# ProProject_flex_ir_golf_2024-07-23.net
KiCad netlist of a schematic drawn in EasyEDA Pro
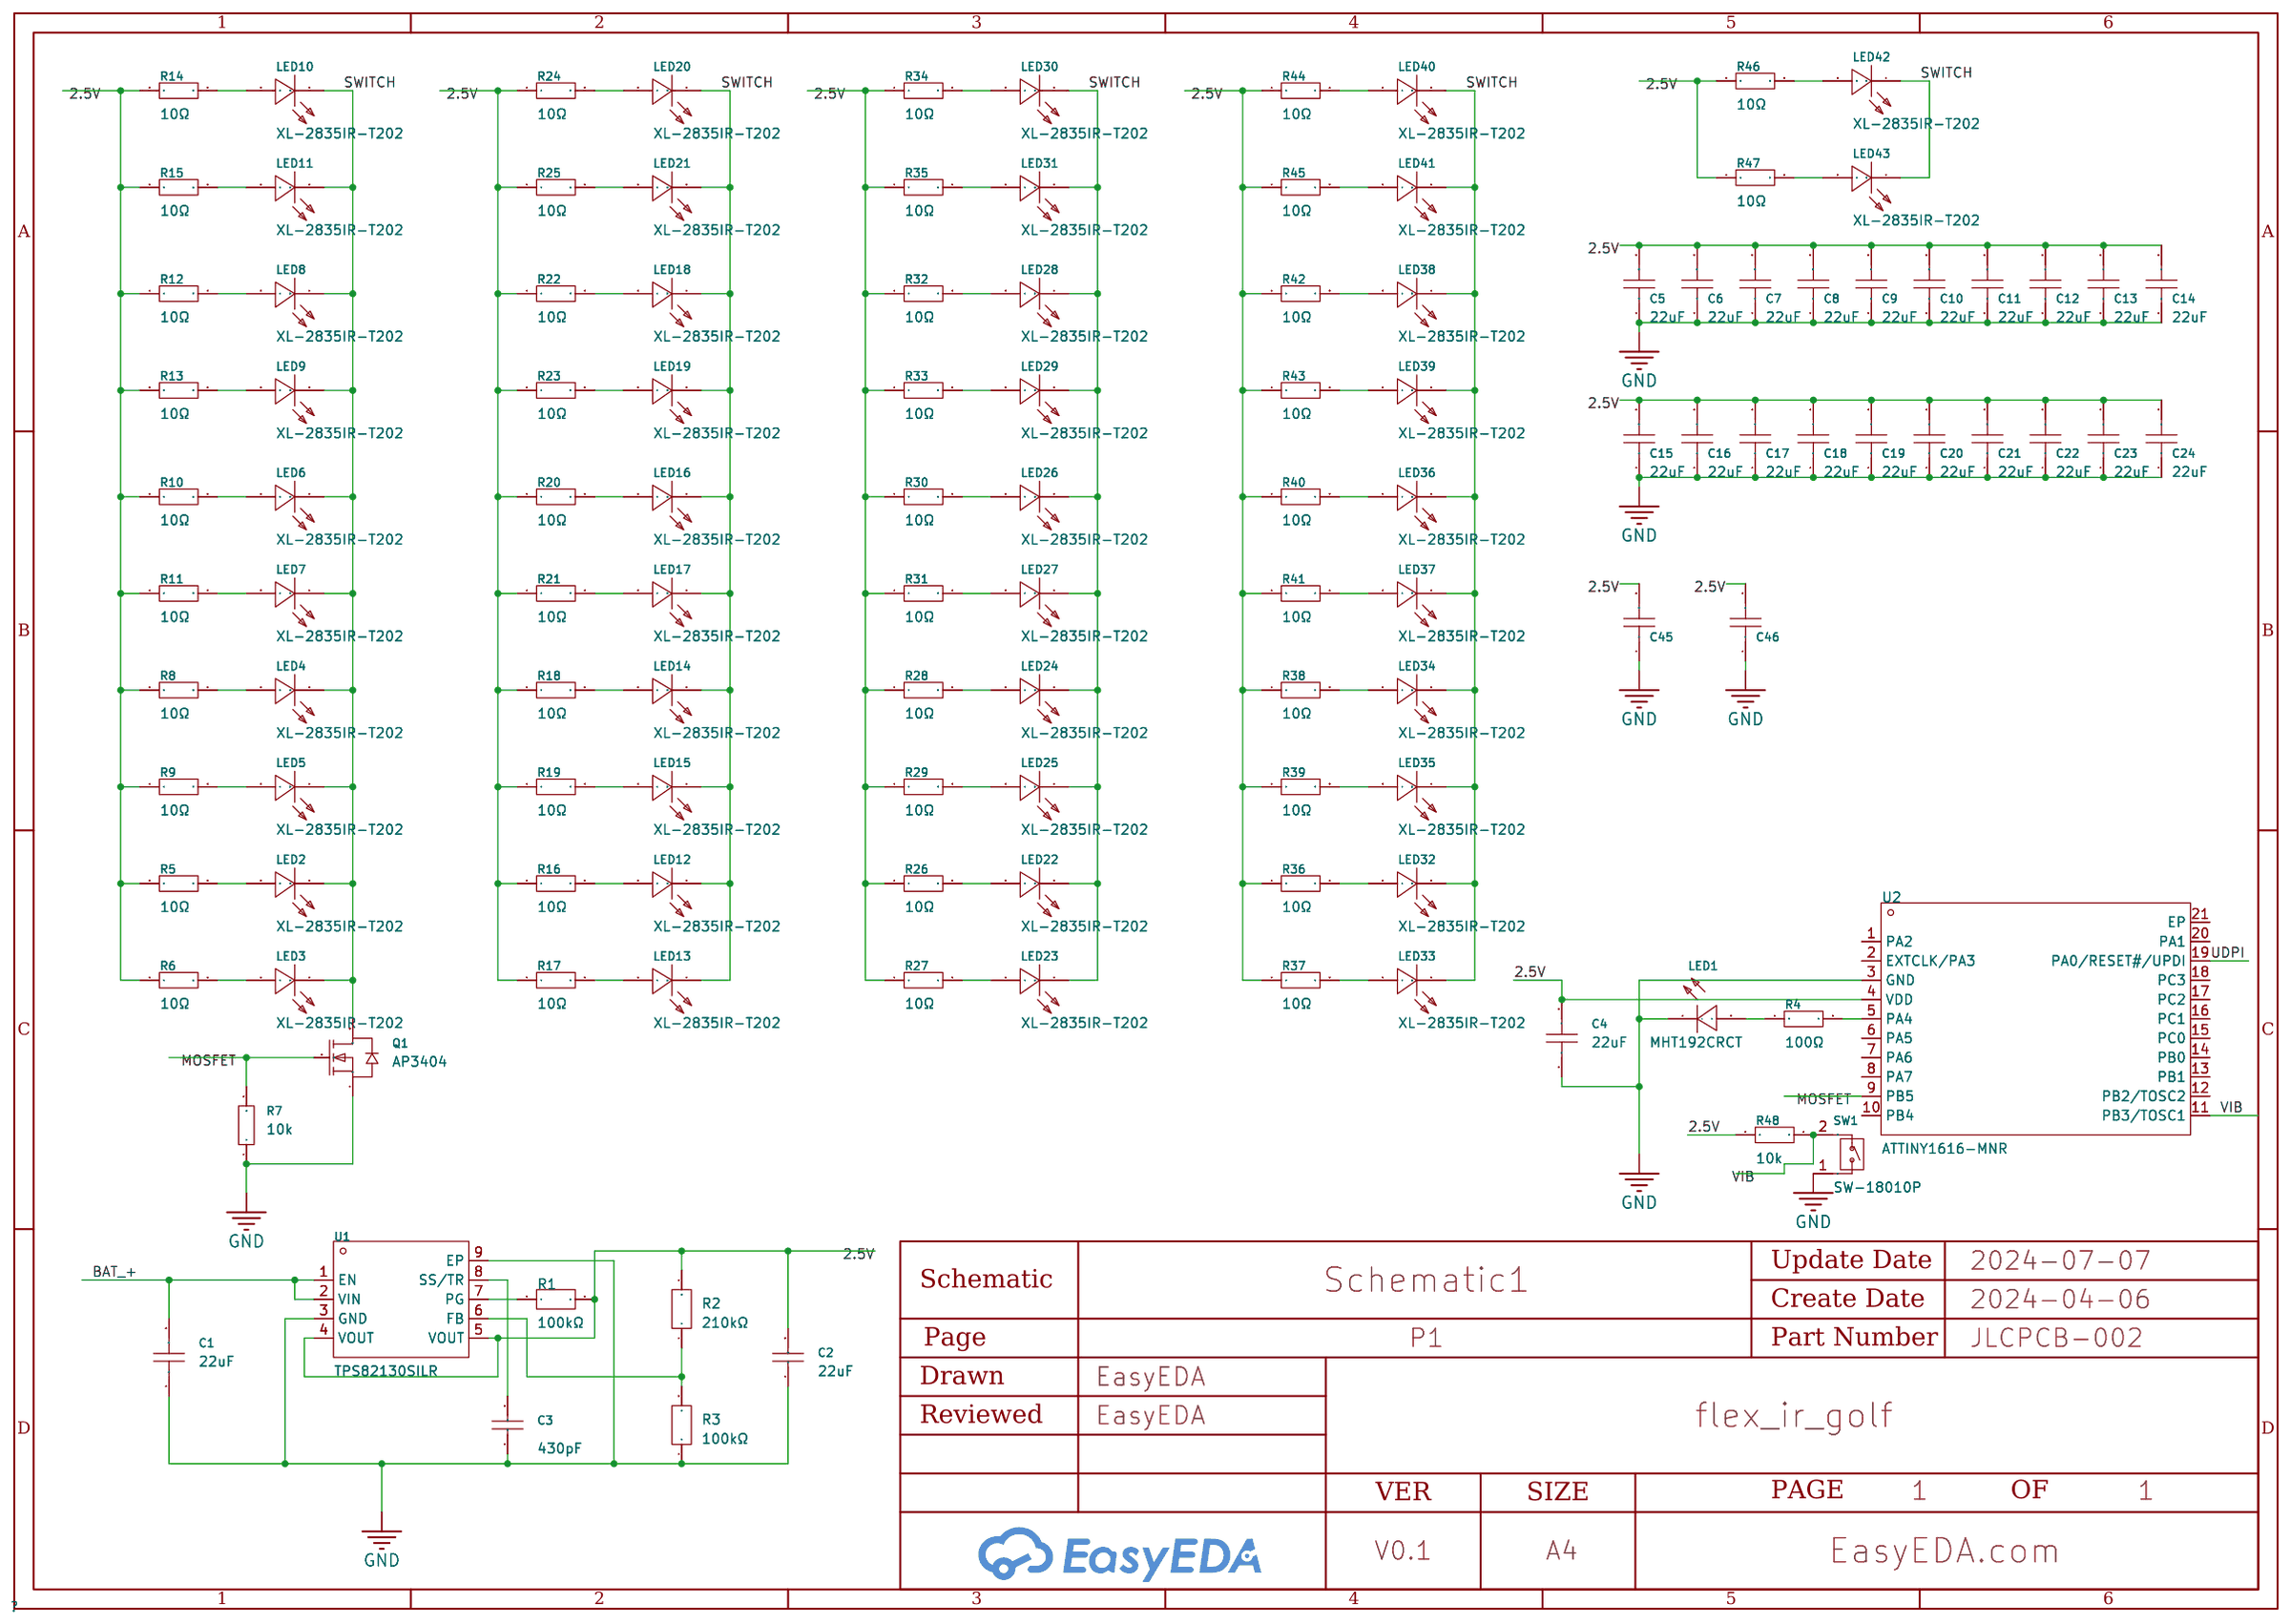
[diagram p0: schematic sheet]

(export (version "E")
  (design (tool "Eeschema 10.0.6"))
  (components
    (comp (ref "C1")
      (value "22uF")
      (footprint "easyedapro:C0603")
      (fields
        (field (name "Manufacturer Part") "GRM188R60J226MEA0D")
        (field (name "Manufacturer") "muRata(村田)")
      )
      (libsource (lib "easyedapro") (part "GRM188R60J226MEA0D"))
    )
    (comp (ref "C2")
      (value "22uF")
      (footprint "easyedapro:C0805")
      (fields
        (field (name "Manufacturer Part") "GRM21BR60J226ME39L")
        (field (name "Manufacturer") "muRata(村田)")
      )
      (libsource (lib "easyedapro") (part "GRM21BR60J226ME39L"))
    )
    (comp (ref "C3")
      (value "1uF")
      (footprint "easyedapro:C0402")
      (fields (field (name "Manufacturer Part") "GRM1555C1H431GA01D"))
      (libsource (lib "easyedapro") (part "CL05A105KP5NNNC"))
    )
    (comp (ref "C4")
      (value "22uF")
      (footprint "easyedapro:C0603")
      (fields
        (field (name "Manufacturer Part") "GRM188R60J226MEA0D")
        (field (name "Manufacturer") "muRata(村田)")
      )
      (libsource (lib "easyedapro") (part "GRM188R60J226MEA0D"))
    )
    (comp (ref "C5")
      (value "22uF")
      (footprint "easyedapro:C0603")
      (fields
        (field (name "Manufacturer Part") "GRM188R60J226MEA0D")
        (field (name "Manufacturer") "muRata(村田)")
      )
      (libsource (lib "easyedapro") (part "GRM188R60J226MEA0D"))
    )
    (comp (ref "C6")
      (value "22uF")
      (footprint "easyedapro:C0603")
      (fields
        (field (name "Manufacturer Part") "GRM188R60J226MEA0D")
        (field (name "Manufacturer") "muRata(村田)")
      )
      (libsource (lib "easyedapro") (part "GRM188R60J226MEA0D"))
    )
    (comp (ref "C7")
      (value "22uF")
      (footprint "easyedapro:C0603")
      (fields
        (field (name "Manufacturer Part") "GRM188R60J226MEA0D")
        (field (name "Manufacturer") "muRata(村田)")
      )
      (libsource (lib "easyedapro") (part "GRM188R60J226MEA0D"))
    )
    (comp (ref "C8")
      (value "22uF")
      (footprint "easyedapro:C0603")
      (fields
        (field (name "Manufacturer Part") "GRM188R60J226MEA0D")
        (field (name "Manufacturer") "muRata(村田)")
      )
      (libsource (lib "easyedapro") (part "GRM188R60J226MEA0D"))
    )
    (comp (ref "C9")
      (value "22uF")
      (footprint "easyedapro:C0603")
      (fields
        (field (name "Manufacturer Part") "GRM188R60J226MEA0D")
        (field (name "Manufacturer") "muRata(村田)")
      )
      (libsource (lib "easyedapro") (part "GRM188R60J226MEA0D"))
    )
    (comp (ref "C10")
      (value "22uF")
      (footprint "easyedapro:C0603")
      (fields
        (field (name "Manufacturer Part") "GRM188R60J226MEA0D")
        (field (name "Manufacturer") "muRata(村田)")
      )
      (libsource (lib "easyedapro") (part "GRM188R60J226MEA0D"))
    )
    (comp (ref "C11")
      (value "22uF")
      (footprint "easyedapro:C0603")
      (fields
        (field (name "Manufacturer Part") "GRM188R60J226MEA0D")
        (field (name "Manufacturer") "muRata(村田)")
      )
      (libsource (lib "easyedapro") (part "GRM188R60J226MEA0D"))
    )
    (comp (ref "C12")
      (value "22uF")
      (footprint "easyedapro:C0603")
      (fields
        (field (name "Manufacturer Part") "GRM188R60J226MEA0D")
        (field (name "Manufacturer") "muRata(村田)")
      )
      (libsource (lib "easyedapro") (part "GRM188R60J226MEA0D"))
    )
    (comp (ref "C13")
      (value "22uF")
      (footprint "easyedapro:C0603")
      (fields
        (field (name "Manufacturer Part") "GRM188R60J226MEA0D")
        (field (name "Manufacturer") "muRata(村田)")
      )
      (libsource (lib "easyedapro") (part "GRM188R60J226MEA0D"))
    )
    (comp (ref "C14")
      (value "22uF")
      (footprint "easyedapro:C0603")
      (fields
        (field (name "Manufacturer Part") "GRM188R60J226MEA0D")
        (field (name "Manufacturer") "muRata(村田)")
      )
      (libsource (lib "easyedapro") (part "GRM188R60J226MEA0D"))
    )
    (comp (ref "C15")
      (value "22uF")
      (footprint "easyedapro:C0603")
      (fields
        (field (name "Manufacturer Part") "GRM188R60J226MEA0D")
        (field (name "Manufacturer") "muRata(村田)")
      )
      (libsource (lib "easyedapro") (part "GRM188R60J226MEA0D"))
    )
    (comp (ref "C16")
      (value "22uF")
      (footprint "easyedapro:C0603")
      (fields
        (field (name "Manufacturer Part") "GRM188R60J226MEA0D")
        (field (name "Manufacturer") "muRata(村田)")
      )
      (libsource (lib "easyedapro") (part "GRM188R60J226MEA0D"))
    )
    (comp (ref "C17")
      (value "22uF")
      (footprint "easyedapro:C0603")
      (fields
        (field (name "Manufacturer Part") "GRM188R60J226MEA0D")
        (field (name "Manufacturer") "muRata(村田)")
      )
      (libsource (lib "easyedapro") (part "GRM188R60J226MEA0D"))
    )
    (comp (ref "C18")
      (value "22uF")
      (footprint "easyedapro:C0603")
      (fields
        (field (name "Manufacturer Part") "GRM188R60J226MEA0D")
        (field (name "Manufacturer") "muRata(村田)")
      )
      (libsource (lib "easyedapro") (part "GRM188R60J226MEA0D"))
    )
    (comp (ref "C19")
      (value "22uF")
      (footprint "easyedapro:C0603")
      (fields
        (field (name "Manufacturer Part") "GRM188R60J226MEA0D")
        (field (name "Manufacturer") "muRata(村田)")
      )
      (libsource (lib "easyedapro") (part "GRM188R60J226MEA0D"))
    )
    (comp (ref "C20")
      (value "22uF")
      (footprint "easyedapro:C0603")
      (fields
        (field (name "Manufacturer Part") "GRM188R60J226MEA0D")
        (field (name "Manufacturer") "muRata(村田)")
      )
      (libsource (lib "easyedapro") (part "GRM188R60J226MEA0D"))
    )
    (comp (ref "C21")
      (value "22uF")
      (footprint "easyedapro:C0603")
      (fields
        (field (name "Manufacturer Part") "GRM188R60J226MEA0D")
        (field (name "Manufacturer") "muRata(村田)")
      )
      (libsource (lib "easyedapro") (part "GRM188R60J226MEA0D"))
    )
    (comp (ref "C22")
      (value "22uF")
      (footprint "easyedapro:C0603")
      (fields
        (field (name "Manufacturer Part") "GRM188R60J226MEA0D")
        (field (name "Manufacturer") "muRata(村田)")
      )
      (libsource (lib "easyedapro") (part "GRM188R60J226MEA0D"))
    )
    (comp (ref "C23")
      (value "22uF")
      (footprint "easyedapro:C0603")
      (fields
        (field (name "Manufacturer Part") "GRM188R60J226MEA0D")
        (field (name "Manufacturer") "muRata(村田)")
      )
      (libsource (lib "easyedapro") (part "GRM188R60J226MEA0D"))
    )
    (comp (ref "C24")
      (value "22uF")
      (footprint "easyedapro:C0603")
      (fields
        (field (name "Manufacturer Part") "GRM188R60J226MEA0D")
        (field (name "Manufacturer") "muRata(村田)")
      )
      (libsource (lib "easyedapro") (part "GRM188R60J226MEA0D"))
    )
    (comp (ref "C45")
      (value "22uF")
      (footprint "easyedapro:C0603")
      (fields
        (field (name "Manufacturer Part") "GRM188R60J226MEA0D")
        (field (name "Manufacturer") "muRata(村田)")
      )
      (libsource (lib "easyedapro") (part "GRM188R60J226MEA0D"))
    )
    (comp (ref "C46")
      (value "22uF")
      (footprint "easyedapro:C0603")
      (fields
        (field (name "Manufacturer Part") "GRM188R60J226MEA0D")
        (field (name "Manufacturer") "muRata(村田)")
      )
      (libsource (lib "easyedapro") (part "GRM188R60J226MEA0D"))
    )
    (comp (ref "LED1")
      (value "MHT192CRCT")
      (footprint "easyedapro:LED0603-RD")
      (fields (field (name "Manufacturer") "MEIHUA(美华)"))
      (libsource (lib "easyedapro") (part "MHT192CRCT"))
    )
    (comp (ref "LED2")
      (value "XL-2835IR-T202")
      (footprint "easyedapro:LED-SMD_L128-XX80CB3500001")
      (description "Emitted Color:White")
      (fields (field (name "Manufacturer") "Lumileds(亮锐)"))
      (libsource (lib "easyedapro") (part "L128-4080CB3500001"))
    )
    (comp (ref "LED3")
      (value "XL-2835IR-T202")
      (footprint "easyedapro:LED-SMD_L128-XX80CB3500001")
      (description "Emitted Color:White")
      (fields (field (name "Manufacturer") "Lumileds(亮锐)"))
      (libsource (lib "easyedapro") (part "L128-4080CB3500001"))
    )
    (comp (ref "LED4")
      (value "XL-2835IR-T202")
      (footprint "easyedapro:LED-SMD_L128-XX80CB3500001")
      (description "Emitted Color:White")
      (fields (field (name "Manufacturer") "Lumileds(亮锐)"))
      (libsource (lib "easyedapro") (part "L128-4080CB3500001"))
    )
    (comp (ref "LED5")
      (value "XL-2835IR-T202")
      (footprint "easyedapro:LED-SMD_L128-XX80CB3500001")
      (description "Emitted Color:White")
      (fields (field (name "Manufacturer") "Lumileds(亮锐)"))
      (libsource (lib "easyedapro") (part "L128-4080CB3500001"))
    )
    (comp (ref "LED6")
      (value "XL-2835IR-T202")
      (footprint "easyedapro:LED-SMD_L128-XX80CB3500001")
      (description "Emitted Color:White")
      (fields (field (name "Manufacturer") "Lumileds(亮锐)"))
      (libsource (lib "easyedapro") (part "L128-4080CB3500001"))
    )
    (comp (ref "LED7")
      (value "XL-2835IR-T202")
      (footprint "easyedapro:LED-SMD_L128-XX80CB3500001")
      (description "Emitted Color:White")
      (fields (field (name "Manufacturer") "Lumileds(亮锐)"))
      (libsource (lib "easyedapro") (part "L128-4080CB3500001"))
    )
    (comp (ref "LED8")
      (value "XL-2835IR-T202")
      (footprint "easyedapro:LED-SMD_L128-XX80CB3500001")
      (description "Emitted Color:White")
      (fields (field (name "Manufacturer") "Lumileds(亮锐)"))
      (libsource (lib "easyedapro") (part "L128-4080CB3500001"))
    )
    (comp (ref "LED9")
      (value "XL-2835IR-T202")
      (footprint "easyedapro:LED-SMD_L128-XX80CB3500001")
      (description "Emitted Color:White")
      (fields (field (name "Manufacturer") "Lumileds(亮锐)"))
      (libsource (lib "easyedapro") (part "L128-4080CB3500001"))
    )
    (comp (ref "LED10")
      (value "XL-2835IR-T202")
      (footprint "easyedapro:LED-SMD_L128-XX80CB3500001")
      (description "Emitted Color:White")
      (fields (field (name "Manufacturer") "Lumileds(亮锐)"))
      (libsource (lib "easyedapro") (part "L128-4080CB3500001"))
    )
    (comp (ref "LED11")
      (value "XL-2835IR-T202")
      (footprint "easyedapro:LED-SMD_L128-XX80CB3500001")
      (description "Emitted Color:White")
      (fields (field (name "Manufacturer") "Lumileds(亮锐)"))
      (libsource (lib "easyedapro") (part "L128-4080CB3500001"))
    )
    (comp (ref "LED12")
      (value "XL-2835IR-T202")
      (footprint "easyedapro:LED-SMD_L128-XX80CB3500001")
      (description "Emitted Color:White")
      (fields (field (name "Manufacturer") "Lumileds(亮锐)"))
      (libsource (lib "easyedapro") (part "L128-4080CB3500001"))
    )
    (comp (ref "LED13")
      (value "XL-2835IR-T202")
      (footprint "easyedapro:LED-SMD_L128-XX80CB3500001")
      (description "Emitted Color:White")
      (fields (field (name "Manufacturer") "Lumileds(亮锐)"))
      (libsource (lib "easyedapro") (part "L128-4080CB3500001"))
    )
    (comp (ref "LED14")
      (value "XL-2835IR-T202")
      (footprint "easyedapro:LED-SMD_L128-XX80CB3500001")
      (description "Emitted Color:White")
      (fields (field (name "Manufacturer") "Lumileds(亮锐)"))
      (libsource (lib "easyedapro") (part "L128-4080CB3500001"))
    )
    (comp (ref "LED15")
      (value "XL-2835IR-T202")
      (footprint "easyedapro:LED-SMD_L128-XX80CB3500001")
      (description "Emitted Color:White")
      (fields (field (name "Manufacturer") "Lumileds(亮锐)"))
      (libsource (lib "easyedapro") (part "L128-4080CB3500001"))
    )
    (comp (ref "LED16")
      (value "XL-2835IR-T202")
      (footprint "easyedapro:LED-SMD_L128-XX80CB3500001")
      (description "Emitted Color:White")
      (fields (field (name "Manufacturer") "Lumileds(亮锐)"))
      (libsource (lib "easyedapro") (part "L128-4080CB3500001"))
    )
    (comp (ref "LED17")
      (value "XL-2835IR-T202")
      (footprint "easyedapro:LED-SMD_L128-XX80CB3500001")
      (description "Emitted Color:White")
      (fields (field (name "Manufacturer") "Lumileds(亮锐)"))
      (libsource (lib "easyedapro") (part "L128-4080CB3500001"))
    )
    (comp (ref "LED18")
      (value "XL-2835IR-T202")
      (footprint "easyedapro:LED-SMD_L128-XX80CB3500001")
      (description "Emitted Color:White")
      (fields (field (name "Manufacturer") "Lumileds(亮锐)"))
      (libsource (lib "easyedapro") (part "L128-4080CB3500001"))
    )
    (comp (ref "LED19")
      (value "XL-2835IR-T202")
      (footprint "easyedapro:LED-SMD_L128-XX80CB3500001")
      (description "Emitted Color:White")
      (fields (field (name "Manufacturer") "Lumileds(亮锐)"))
      (libsource (lib "easyedapro") (part "L128-4080CB3500001"))
    )
    (comp (ref "LED20")
      (value "XL-2835IR-T202")
      (footprint "easyedapro:LED-SMD_L128-XX80CB3500001")
      (description "Emitted Color:White")
      (fields (field (name "Manufacturer") "Lumileds(亮锐)"))
      (libsource (lib "easyedapro") (part "L128-4080CB3500001"))
    )
    (comp (ref "LED21")
      (value "XL-2835IR-T202")
      (footprint "easyedapro:LED-SMD_L128-XX80CB3500001")
      (description "Emitted Color:White")
      (fields (field (name "Manufacturer") "Lumileds(亮锐)"))
      (libsource (lib "easyedapro") (part "L128-4080CB3500001"))
    )
    (comp (ref "LED22")
      (value "XL-2835IR-T202")
      (footprint "easyedapro:LED-SMD_L128-XX80CB3500001")
      (description "Emitted Color:White")
      (fields (field (name "Manufacturer") "Lumileds(亮锐)"))
      (libsource (lib "easyedapro") (part "L128-4080CB3500001"))
    )
    (comp (ref "LED23")
      (value "XL-2835IR-T202")
      (footprint "easyedapro:LED-SMD_L128-XX80CB3500001")
      (description "Emitted Color:White")
      (fields (field (name "Manufacturer") "Lumileds(亮锐)"))
      (libsource (lib "easyedapro") (part "L128-4080CB3500001"))
    )
    (comp (ref "LED24")
      (value "XL-2835IR-T202")
      (footprint "easyedapro:LED-SMD_L128-XX80CB3500001")
      (description "Emitted Color:White")
      (fields (field (name "Manufacturer") "Lumileds(亮锐)"))
      (libsource (lib "easyedapro") (part "L128-4080CB3500001"))
    )
    (comp (ref "LED25")
      (value "XL-2835IR-T202")
      (footprint "easyedapro:LED-SMD_L128-XX80CB3500001")
      (description "Emitted Color:White")
      (fields (field (name "Manufacturer") "Lumileds(亮锐)"))
      (libsource (lib "easyedapro") (part "L128-4080CB3500001"))
    )
    (comp (ref "LED26")
      (value "XL-2835IR-T202")
      (footprint "easyedapro:LED-SMD_L128-XX80CB3500001")
      (description "Emitted Color:White")
      (fields (field (name "Manufacturer") "Lumileds(亮锐)"))
      (libsource (lib "easyedapro") (part "L128-4080CB3500001"))
    )
    (comp (ref "LED27")
      (value "XL-2835IR-T202")
      (footprint "easyedapro:LED-SMD_L128-XX80CB3500001")
      (description "Emitted Color:White")
      (fields (field (name "Manufacturer") "Lumileds(亮锐)"))
      (libsource (lib "easyedapro") (part "L128-4080CB3500001"))
    )
    (comp (ref "LED28")
      (value "XL-2835IR-T202")
      (footprint "easyedapro:LED-SMD_L128-XX80CB3500001")
      (description "Emitted Color:White")
      (fields (field (name "Manufacturer") "Lumileds(亮锐)"))
      (libsource (lib "easyedapro") (part "L128-4080CB3500001"))
    )
    (comp (ref "LED29")
      (value "XL-2835IR-T202")
      (footprint "easyedapro:LED-SMD_L128-XX80CB3500001")
      (description "Emitted Color:White")
      (fields (field (name "Manufacturer") "Lumileds(亮锐)"))
      (libsource (lib "easyedapro") (part "L128-4080CB3500001"))
    )
    (comp (ref "LED30")
      (value "XL-2835IR-T202")
      (footprint "easyedapro:LED-SMD_L128-XX80CB3500001")
      (description "Emitted Color:White")
      (fields (field (name "Manufacturer") "Lumileds(亮锐)"))
      (libsource (lib "easyedapro") (part "L128-4080CB3500001"))
    )
    (comp (ref "LED31")
      (value "XL-2835IR-T202")
      (footprint "easyedapro:LED-SMD_L128-XX80CB3500001")
      (description "Emitted Color:White")
      (fields (field (name "Manufacturer") "Lumileds(亮锐)"))
      (libsource (lib "easyedapro") (part "L128-4080CB3500001"))
    )
    (comp (ref "LED32")
      (value "XL-2835IR-T202")
      (footprint "easyedapro:LED-SMD_L128-XX80CB3500001")
      (description "Emitted Color:White")
      (fields (field (name "Manufacturer") "Lumileds(亮锐)"))
      (libsource (lib "easyedapro") (part "L128-4080CB3500001"))
    )
    (comp (ref "LED33")
      (value "XL-2835IR-T202")
      (footprint "easyedapro:LED-SMD_L128-XX80CB3500001")
      (description "Emitted Color:White")
      (fields (field (name "Manufacturer") "Lumileds(亮锐)"))
      (libsource (lib "easyedapro") (part "L128-4080CB3500001"))
    )
    (comp (ref "LED34")
      (value "XL-2835IR-T202")
      (footprint "easyedapro:LED-SMD_L128-XX80CB3500001")
      (description "Emitted Color:White")
      (fields (field (name "Manufacturer") "Lumileds(亮锐)"))
      (libsource (lib "easyedapro") (part "L128-4080CB3500001"))
    )
    (comp (ref "LED35")
      (value "XL-2835IR-T202")
      (footprint "easyedapro:LED-SMD_L128-XX80CB3500001")
      (description "Emitted Color:White")
      (fields (field (name "Manufacturer") "Lumileds(亮锐)"))
      (libsource (lib "easyedapro") (part "L128-4080CB3500001"))
    )
    (comp (ref "LED36")
      (value "XL-2835IR-T202")
      (footprint "easyedapro:LED-SMD_L128-XX80CB3500001")
      (description "Emitted Color:White")
      (fields (field (name "Manufacturer") "Lumileds(亮锐)"))
      (libsource (lib "easyedapro") (part "L128-4080CB3500001"))
    )
    (comp (ref "LED37")
      (value "XL-2835IR-T202")
      (footprint "easyedapro:LED-SMD_L128-XX80CB3500001")
      (description "Emitted Color:White")
      (fields (field (name "Manufacturer") "Lumileds(亮锐)"))
      (libsource (lib "easyedapro") (part "L128-4080CB3500001"))
    )
    (comp (ref "LED38")
      (value "XL-2835IR-T202")
      (footprint "easyedapro:LED-SMD_L128-XX80CB3500001")
      (description "Emitted Color:White")
      (fields (field (name "Manufacturer") "Lumileds(亮锐)"))
      (libsource (lib "easyedapro") (part "L128-4080CB3500001"))
    )
    (comp (ref "LED39")
      (value "XL-2835IR-T202")
      (footprint "easyedapro:LED-SMD_L128-XX80CB3500001")
      (description "Emitted Color:White")
      (fields (field (name "Manufacturer") "Lumileds(亮锐)"))
      (libsource (lib "easyedapro") (part "L128-4080CB3500001"))
    )
    (comp (ref "LED40")
      (value "XL-2835IR-T202")
      (footprint "easyedapro:LED-SMD_L128-XX80CB3500001")
      (description "Emitted Color:White")
      (fields (field (name "Manufacturer") "Lumileds(亮锐)"))
      (libsource (lib "easyedapro") (part "L128-4080CB3500001"))
    )
    (comp (ref "LED41")
      (value "XL-2835IR-T202")
      (footprint "easyedapro:LED-SMD_L128-XX80CB3500001")
      (description "Emitted Color:White")
      (fields (field (name "Manufacturer") "Lumileds(亮锐)"))
      (libsource (lib "easyedapro") (part "L128-4080CB3500001"))
    )
    (comp (ref "LED42")
      (value "XL-2835IR-T202")
      (footprint "easyedapro:LED-SMD_L128-XX80CB3500001")
      (description "Emitted Color:White")
      (fields (field (name "Manufacturer") "Lumileds(亮锐)"))
      (libsource (lib "easyedapro") (part "L128-4080CB3500001"))
    )
    (comp (ref "LED43")
      (value "XL-2835IR-T202")
      (footprint "easyedapro:LED-SMD_L128-XX80CB3500001")
      (description "Emitted Color:White")
      (fields (field (name "Manufacturer") "Lumileds(亮锐)"))
      (libsource (lib "easyedapro") (part "L128-4080CB3500001"))
    )
    (comp (ref "Q1")
      (value "AP3404")
      (footprint "easyedapro:SOT-23-3_L2.9-W1.3-P1.90-LS2.4-BR-2")
      (fields (field (name "Manufacturer") "ALLPOWER(铨力)"))
      (libsource (lib "easyedapro") (part "AP3404"))
    )
    (comp (ref "R1")
      (value "100kΩ")
      (footprint "easyedapro:R0402")
      (fields
        (field (name "Manufacturer Part") "CRCW0402100KFKED")
        (field (name "Manufacturer") "VISHAY(威世)")
      )
      (libsource (lib "easyedapro") (part "CRCW0402100KFKED"))
    )
    (comp (ref "R2")
      (value "210kΩ")
      (footprint "easyedapro:R0402")
      (fields
        (field (name "Manufacturer Part") "CRCW0402210KFKED")
        (field (name "Manufacturer") "VISHAY(威世)")
      )
      (libsource (lib "easyedapro") (part "CRCW0402210KFKED"))
    )
    (comp (ref "R3")
      (value "100kΩ")
      (footprint "easyedapro:R0402")
      (fields
        (field (name "Manufacturer Part") "CRCW0402100KFKED")
        (field (name "Manufacturer") "VISHAY(威世)")
      )
      (libsource (lib "easyedapro") (part "CRCW0402100KFKED"))
    )
    (comp (ref "R4")
      (value "100Ω")
      (footprint "easyedapro:R0402")
      (fields
        (field (name "Manufacturer Part") "0402WGF1000TCE")
        (field (name "Manufacturer") "UNI-ROYAL(厚声)")
      )
      (libsource (lib "easyedapro") (part "0402WGF1000TCE"))
    )
    (comp (ref "R5")
      (value "10Ω")
      (footprint "easyedapro:R0603")
      (fields
        (field (name "Manufacturer Part") "0603WAF100JT5E")
        (field (name "Manufacturer") "UNI-ROYAL(厚声)")
      )
      (libsource (lib "easyedapro") (part "0603WAF100JT5E"))
    )
    (comp (ref "R6")
      (value "10Ω")
      (footprint "easyedapro:R0603")
      (fields
        (field (name "Manufacturer Part") "0603WAF100JT5E")
        (field (name "Manufacturer") "UNI-ROYAL(厚声)")
      )
      (libsource (lib "easyedapro") (part "0603WAF100JT5E"))
    )
    (comp (ref "R7")
      (value "10k")
      (footprint "easyedapro:R0603")
      (fields
        (field (name "Manufacturer Part") "0603WAF100JT5E")
        (field (name "Manufacturer") "UNI-ROYAL(厚声)")
      )
      (libsource (lib "easyedapro") (part "0603WAF100JT5E"))
    )
    (comp (ref "R8")
      (value "10Ω")
      (footprint "easyedapro:R0603")
      (fields
        (field (name "Manufacturer Part") "0603WAF100JT5E")
        (field (name "Manufacturer") "UNI-ROYAL(厚声)")
      )
      (libsource (lib "easyedapro") (part "0603WAF100JT5E"))
    )
    (comp (ref "R9")
      (value "10Ω")
      (footprint "easyedapro:R0603")
      (fields
        (field (name "Manufacturer Part") "0603WAF100JT5E")
        (field (name "Manufacturer") "UNI-ROYAL(厚声)")
      )
      (libsource (lib "easyedapro") (part "0603WAF100JT5E"))
    )
    (comp (ref "R10")
      (value "10Ω")
      (footprint "easyedapro:R0603")
      (fields
        (field (name "Manufacturer Part") "0603WAF100JT5E")
        (field (name "Manufacturer") "UNI-ROYAL(厚声)")
      )
      (libsource (lib "easyedapro") (part "0603WAF100JT5E"))
    )
    (comp (ref "R11")
      (value "10Ω")
      (footprint "easyedapro:R0603")
      (fields
        (field (name "Manufacturer Part") "0603WAF100JT5E")
        (field (name "Manufacturer") "UNI-ROYAL(厚声)")
      )
      (libsource (lib "easyedapro") (part "0603WAF100JT5E"))
    )
    (comp (ref "R12")
      (value "10Ω")
      (footprint "easyedapro:R0603")
      (fields
        (field (name "Manufacturer Part") "0603WAF100JT5E")
        (field (name "Manufacturer") "UNI-ROYAL(厚声)")
      )
      (libsource (lib "easyedapro") (part "0603WAF100JT5E"))
    )
    (comp (ref "R13")
      (value "10Ω")
      (footprint "easyedapro:R0603")
      (fields
        (field (name "Manufacturer Part") "0603WAF100JT5E")
        (field (name "Manufacturer") "UNI-ROYAL(厚声)")
      )
      (libsource (lib "easyedapro") (part "0603WAF100JT5E"))
    )
    (comp (ref "R14")
      (value "10Ω")
      (footprint "easyedapro:R0603")
      (fields
        (field (name "Manufacturer Part") "0603WAF100JT5E")
        (field (name "Manufacturer") "UNI-ROYAL(厚声)")
      )
      (libsource (lib "easyedapro") (part "0603WAF100JT5E"))
    )
    (comp (ref "R15")
      (value "10Ω")
      (footprint "easyedapro:R0603")
      (fields
        (field (name "Manufacturer Part") "0603WAF100JT5E")
        (field (name "Manufacturer") "UNI-ROYAL(厚声)")
      )
      (libsource (lib "easyedapro") (part "0603WAF100JT5E"))
    )
    (comp (ref "R16")
      (value "10Ω")
      (footprint "easyedapro:R0603")
      (fields
        (field (name "Manufacturer Part") "0603WAF100JT5E")
        (field (name "Manufacturer") "UNI-ROYAL(厚声)")
      )
      (libsource (lib "easyedapro") (part "0603WAF100JT5E"))
    )
    (comp (ref "R17")
      (value "10Ω")
      (footprint "easyedapro:R0603")
      (fields
        (field (name "Manufacturer Part") "0603WAF100JT5E")
        (field (name "Manufacturer") "UNI-ROYAL(厚声)")
      )
      (libsource (lib "easyedapro") (part "0603WAF100JT5E"))
    )
    (comp (ref "R18")
      (value "10Ω")
      (footprint "easyedapro:R0603")
      (fields
        (field (name "Manufacturer Part") "0603WAF100JT5E")
        (field (name "Manufacturer") "UNI-ROYAL(厚声)")
      )
      (libsource (lib "easyedapro") (part "0603WAF100JT5E"))
    )
    (comp (ref "R19")
      (value "10Ω")
      (footprint "easyedapro:R0603")
      (fields
        (field (name "Manufacturer Part") "0603WAF100JT5E")
        (field (name "Manufacturer") "UNI-ROYAL(厚声)")
      )
      (libsource (lib "easyedapro") (part "0603WAF100JT5E"))
    )
    (comp (ref "R20")
      (value "10Ω")
      (footprint "easyedapro:R0603")
      (fields
        (field (name "Manufacturer Part") "0603WAF100JT5E")
        (field (name "Manufacturer") "UNI-ROYAL(厚声)")
      )
      (libsource (lib "easyedapro") (part "0603WAF100JT5E"))
    )
    (comp (ref "R21")
      (value "10Ω")
      (footprint "easyedapro:R0603")
      (fields
        (field (name "Manufacturer Part") "0603WAF100JT5E")
        (field (name "Manufacturer") "UNI-ROYAL(厚声)")
      )
      (libsource (lib "easyedapro") (part "0603WAF100JT5E"))
    )
    (comp (ref "R22")
      (value "10Ω")
      (footprint "easyedapro:R0603")
      (fields
        (field (name "Manufacturer Part") "0603WAF100JT5E")
        (field (name "Manufacturer") "UNI-ROYAL(厚声)")
      )
      (libsource (lib "easyedapro") (part "0603WAF100JT5E"))
    )
    (comp (ref "R23")
      (value "10Ω")
      (footprint "easyedapro:R0603")
      (fields
        (field (name "Manufacturer Part") "0603WAF100JT5E")
        (field (name "Manufacturer") "UNI-ROYAL(厚声)")
      )
      (libsource (lib "easyedapro") (part "0603WAF100JT5E"))
    )
    (comp (ref "R24")
      (value "10Ω")
      (footprint "easyedapro:R0603")
      (fields
        (field (name "Manufacturer Part") "0603WAF100JT5E")
        (field (name "Manufacturer") "UNI-ROYAL(厚声)")
      )
      (libsource (lib "easyedapro") (part "0603WAF100JT5E"))
    )
    (comp (ref "R25")
      (value "10Ω")
      (footprint "easyedapro:R0603")
      (fields
        (field (name "Manufacturer Part") "0603WAF100JT5E")
        (field (name "Manufacturer") "UNI-ROYAL(厚声)")
      )
      (libsource (lib "easyedapro") (part "0603WAF100JT5E"))
    )
    (comp (ref "R26")
      (value "10Ω")
      (footprint "easyedapro:R0603")
      (fields
        (field (name "Manufacturer Part") "0603WAF100JT5E")
        (field (name "Manufacturer") "UNI-ROYAL(厚声)")
      )
      (libsource (lib "easyedapro") (part "0603WAF100JT5E"))
    )
    (comp (ref "R27")
      (value "10Ω")
      (footprint "easyedapro:R0603")
      (fields
        (field (name "Manufacturer Part") "0603WAF100JT5E")
        (field (name "Manufacturer") "UNI-ROYAL(厚声)")
      )
      (libsource (lib "easyedapro") (part "0603WAF100JT5E"))
    )
    (comp (ref "R28")
      (value "10Ω")
      (footprint "easyedapro:R0603")
      (fields
        (field (name "Manufacturer Part") "0603WAF100JT5E")
        (field (name "Manufacturer") "UNI-ROYAL(厚声)")
      )
      (libsource (lib "easyedapro") (part "0603WAF100JT5E"))
    )
    (comp (ref "R29")
      (value "10Ω")
      (footprint "easyedapro:R0603")
      (fields
        (field (name "Manufacturer Part") "0603WAF100JT5E")
        (field (name "Manufacturer") "UNI-ROYAL(厚声)")
      )
      (libsource (lib "easyedapro") (part "0603WAF100JT5E"))
    )
    (comp (ref "R30")
      (value "10Ω")
      (footprint "easyedapro:R0603")
      (fields
        (field (name "Manufacturer Part") "0603WAF100JT5E")
        (field (name "Manufacturer") "UNI-ROYAL(厚声)")
      )
      (libsource (lib "easyedapro") (part "0603WAF100JT5E"))
    )
    (comp (ref "R31")
      (value "10Ω")
      (footprint "easyedapro:R0603")
      (fields
        (field (name "Manufacturer Part") "0603WAF100JT5E")
        (field (name "Manufacturer") "UNI-ROYAL(厚声)")
      )
      (libsource (lib "easyedapro") (part "0603WAF100JT5E"))
    )
    (comp (ref "R32")
      (value "10Ω")
      (footprint "easyedapro:R0603")
      (fields
        (field (name "Manufacturer Part") "0603WAF100JT5E")
        (field (name "Manufacturer") "UNI-ROYAL(厚声)")
      )
      (libsource (lib "easyedapro") (part "0603WAF100JT5E"))
    )
    (comp (ref "R33")
      (value "10Ω")
      (footprint "easyedapro:R0603")
      (fields
        (field (name "Manufacturer Part") "0603WAF100JT5E")
        (field (name "Manufacturer") "UNI-ROYAL(厚声)")
      )
      (libsource (lib "easyedapro") (part "0603WAF100JT5E"))
    )
    (comp (ref "R34")
      (value "10Ω")
      (footprint "easyedapro:R0603")
      (fields
        (field (name "Manufacturer Part") "0603WAF100JT5E")
        (field (name "Manufacturer") "UNI-ROYAL(厚声)")
      )
      (libsource (lib "easyedapro") (part "0603WAF100JT5E"))
    )
    (comp (ref "R35")
      (value "10Ω")
      (footprint "easyedapro:R0603")
      (fields
        (field (name "Manufacturer Part") "0603WAF100JT5E")
        (field (name "Manufacturer") "UNI-ROYAL(厚声)")
      )
      (libsource (lib "easyedapro") (part "0603WAF100JT5E"))
    )
    (comp (ref "R36")
      (value "10Ω")
      (footprint "easyedapro:R0603")
      (fields
        (field (name "Manufacturer Part") "0603WAF100JT5E")
        (field (name "Manufacturer") "UNI-ROYAL(厚声)")
      )
      (libsource (lib "easyedapro") (part "0603WAF100JT5E"))
    )
    (comp (ref "R37")
      (value "10Ω")
      (footprint "easyedapro:R0603")
      (fields
        (field (name "Manufacturer Part") "0603WAF100JT5E")
        (field (name "Manufacturer") "UNI-ROYAL(厚声)")
      )
      (libsource (lib "easyedapro") (part "0603WAF100JT5E"))
    )
    (comp (ref "R38")
      (value "10Ω")
      (footprint "easyedapro:R0603")
      (fields
        (field (name "Manufacturer Part") "0603WAF100JT5E")
        (field (name "Manufacturer") "UNI-ROYAL(厚声)")
      )
      (libsource (lib "easyedapro") (part "0603WAF100JT5E"))
    )
    (comp (ref "R39")
      (value "10Ω")
      (footprint "easyedapro:R0603")
      (fields
        (field (name "Manufacturer Part") "0603WAF100JT5E")
        (field (name "Manufacturer") "UNI-ROYAL(厚声)")
      )
      (libsource (lib "easyedapro") (part "0603WAF100JT5E"))
    )
    (comp (ref "R40")
      (value "10Ω")
      (footprint "easyedapro:R0603")
      (fields
        (field (name "Manufacturer Part") "0603WAF100JT5E")
        (field (name "Manufacturer") "UNI-ROYAL(厚声)")
      )
      (libsource (lib "easyedapro") (part "0603WAF100JT5E"))
    )
    (comp (ref "R41")
      (value "10Ω")
      (footprint "easyedapro:R0603")
      (fields
        (field (name "Manufacturer Part") "0603WAF100JT5E")
        (field (name "Manufacturer") "UNI-ROYAL(厚声)")
      )
      (libsource (lib "easyedapro") (part "0603WAF100JT5E"))
    )
    (comp (ref "R42")
      (value "10Ω")
      (footprint "easyedapro:R0603")
      (fields
        (field (name "Manufacturer Part") "0603WAF100JT5E")
        (field (name "Manufacturer") "UNI-ROYAL(厚声)")
      )
      (libsource (lib "easyedapro") (part "0603WAF100JT5E"))
    )
    (comp (ref "R43")
      (value "10Ω")
      (footprint "easyedapro:R0603")
      (fields
        (field (name "Manufacturer Part") "0603WAF100JT5E")
        (field (name "Manufacturer") "UNI-ROYAL(厚声)")
      )
      (libsource (lib "easyedapro") (part "0603WAF100JT5E"))
    )
    (comp (ref "R44")
      (value "10Ω")
      (footprint "easyedapro:R0603")
      (fields
        (field (name "Manufacturer Part") "0603WAF100JT5E")
        (field (name "Manufacturer") "UNI-ROYAL(厚声)")
      )
      (libsource (lib "easyedapro") (part "0603WAF100JT5E"))
    )
    (comp (ref "R45")
      (value "10Ω")
      (footprint "easyedapro:R0603")
      (fields
        (field (name "Manufacturer Part") "0603WAF100JT5E")
        (field (name "Manufacturer") "UNI-ROYAL(厚声)")
      )
      (libsource (lib "easyedapro") (part "0603WAF100JT5E"))
    )
    (comp (ref "R46")
      (value "10Ω")
      (footprint "easyedapro:R0603")
      (fields
        (field (name "Manufacturer Part") "0603WAF100JT5E")
        (field (name "Manufacturer") "UNI-ROYAL(厚声)")
      )
      (libsource (lib "easyedapro") (part "0603WAF100JT5E"))
    )
    (comp (ref "R47")
      (value "10Ω")
      (footprint "easyedapro:R0603")
      (fields
        (field (name "Manufacturer Part") "0603WAF100JT5E")
        (field (name "Manufacturer") "UNI-ROYAL(厚声)")
      )
      (libsource (lib "easyedapro") (part "0603WAF100JT5E"))
    )
    (comp (ref "R48")
      (value "10k")
      (footprint "easyedapro:R0603")
      (fields
        (field (name "Manufacturer Part") "0603WAF100JT5E")
        (field (name "Manufacturer") "UNI-ROYAL(厚声)")
      )
      (libsource (lib "easyedapro") (part "0603WAF100JT5E"))
    )
    (comp (ref "SW1")
      (value "SW-18010P")
      (footprint "easyedapro:SW-TH_SW-18010P")
      (fields (field (name "Manufacturer") "SHOU HAN(首韩)"))
      (libsource (lib "easyedapro") (part "SW-18010P"))
    )
    (comp (ref "U1")
      (value "TPS82130SILR")
      (footprint "easyedapro:USIP-8_L3.0-W2.8-P0.65-TL-EP")
      (fields (field (name "Manufacturer") "TI(德州仪器)"))
      (libsource (lib "easyedapro") (part "TPS82130SILR"))
    )
    (comp (ref "U2")
      (value "ATTINY1616-MNR")
      (footprint "easyedapro:QFN-20_L3.0-W3.0-P0.40-BL-EP1.7")
      (fields (field (name "Manufacturer") "MICROCHIP(美国微芯)"))
      (libsource (lib "easyedapro") (part "ATTINY1616-MNR"))
    )
  )
  (nets
    (net (code "1") (name "/2.5V") (class "Default")
      (node (ref "C10") (pin "2") (pinfunction "2_2") (pintype "input"))
      (node (ref "C11") (pin "2") (pinfunction "2_2") (pintype "input"))
      (node (ref "C12") (pin "2") (pinfunction "2_2") (pintype "input"))
      (node (ref "C13") (pin "2") (pinfunction "2_2") (pintype "input"))
      (node (ref "C14") (pin "2") (pinfunction "2_2") (pintype "input"))
      (node (ref "C15") (pin "2") (pinfunction "2_2") (pintype "input"))
      (node (ref "C16") (pin "2") (pinfunction "2_2") (pintype "input"))
      (node (ref "C17") (pin "2") (pinfunction "2_2") (pintype "input"))
      (node (ref "C18") (pin "2") (pinfunction "2_2") (pintype "input"))
      (node (ref "C19") (pin "2") (pinfunction "2_2") (pintype "input"))
      (node (ref "C2") (pin "2") (pinfunction "2_2") (pintype "input"))
      (node (ref "C20") (pin "2") (pinfunction "2_2") (pintype "input"))
      (node (ref "C21") (pin "2") (pinfunction "2_2") (pintype "input"))
      (node (ref "C22") (pin "2") (pinfunction "2_2") (pintype "input"))
      (node (ref "C23") (pin "2") (pinfunction "2_2") (pintype "input"))
      (node (ref "C24") (pin "2") (pinfunction "2_2") (pintype "input"))
      (node (ref "C4") (pin "2") (pinfunction "2_2") (pintype "input"))
      (node (ref "C45") (pin "2") (pinfunction "2_2") (pintype "input"))
      (node (ref "C46") (pin "2") (pinfunction "2_2") (pintype "input"))
      (node (ref "C5") (pin "2") (pinfunction "2_2") (pintype "input"))
      (node (ref "C6") (pin "2") (pinfunction "2_2") (pintype "input"))
      (node (ref "C7") (pin "2") (pinfunction "2_2") (pintype "input"))
      (node (ref "C8") (pin "2") (pinfunction "2_2") (pintype "input"))
      (node (ref "C9") (pin "2") (pinfunction "2_2") (pintype "input"))
      (node (ref "R1") (pin "2") (pinfunction "2_2") (pintype "unspecified"))
      (node (ref "R10") (pin "1") (pinfunction "1_1") (pintype "input"))
      (node (ref "R11") (pin "1") (pinfunction "1_1") (pintype "input"))
      (node (ref "R12") (pin "1") (pinfunction "1_1") (pintype "input"))
      (node (ref "R13") (pin "1") (pinfunction "1_1") (pintype "input"))
      (node (ref "R14") (pin "1") (pinfunction "1_1") (pintype "input"))
      (node (ref "R15") (pin "1") (pinfunction "1_1") (pintype "input"))
      (node (ref "R16") (pin "1") (pinfunction "1_1") (pintype "input"))
      (node (ref "R17") (pin "1") (pinfunction "1_1") (pintype "input"))
      (node (ref "R18") (pin "1") (pinfunction "1_1") (pintype "input"))
      (node (ref "R19") (pin "1") (pinfunction "1_1") (pintype "input"))
      (node (ref "R2") (pin "2") (pinfunction "2_2") (pintype "input"))
      (node (ref "R20") (pin "1") (pinfunction "1_1") (pintype "input"))
      (node (ref "R21") (pin "1") (pinfunction "1_1") (pintype "input"))
      (node (ref "R22") (pin "1") (pinfunction "1_1") (pintype "input"))
      (node (ref "R23") (pin "1") (pinfunction "1_1") (pintype "input"))
      (node (ref "R24") (pin "1") (pinfunction "1_1") (pintype "input"))
      (node (ref "R25") (pin "1") (pinfunction "1_1") (pintype "input"))
      (node (ref "R26") (pin "1") (pinfunction "1_1") (pintype "input"))
      (node (ref "R27") (pin "1") (pinfunction "1_1") (pintype "input"))
      (node (ref "R28") (pin "1") (pinfunction "1_1") (pintype "input"))
      (node (ref "R29") (pin "1") (pinfunction "1_1") (pintype "input"))
      (node (ref "R30") (pin "1") (pinfunction "1_1") (pintype "input"))
      (node (ref "R31") (pin "1") (pinfunction "1_1") (pintype "input"))
      (node (ref "R32") (pin "1") (pinfunction "1_1") (pintype "input"))
      (node (ref "R33") (pin "1") (pinfunction "1_1") (pintype "input"))
      (node (ref "R34") (pin "1") (pinfunction "1_1") (pintype "input"))
      (node (ref "R35") (pin "1") (pinfunction "1_1") (pintype "input"))
      (node (ref "R36") (pin "1") (pinfunction "1_1") (pintype "input"))
      (node (ref "R37") (pin "1") (pinfunction "1_1") (pintype "input"))
      (node (ref "R38") (pin "1") (pinfunction "1_1") (pintype "input"))
      (node (ref "R39") (pin "1") (pinfunction "1_1") (pintype "input"))
      (node (ref "R40") (pin "1") (pinfunction "1_1") (pintype "input"))
      (node (ref "R41") (pin "1") (pinfunction "1_1") (pintype "input"))
      (node (ref "R42") (pin "1") (pinfunction "1_1") (pintype "input"))
      (node (ref "R43") (pin "1") (pinfunction "1_1") (pintype "input"))
      (node (ref "R44") (pin "1") (pinfunction "1_1") (pintype "input"))
      (node (ref "R45") (pin "1") (pinfunction "1_1") (pintype "input"))
      (node (ref "R46") (pin "1") (pinfunction "1_1") (pintype "input"))
      (node (ref "R47") (pin "1") (pinfunction "1_1") (pintype "input"))
      (node (ref "R48") (pin "2") (pinfunction "2_2") (pintype "input"))
      (node (ref "R5") (pin "1") (pinfunction "1_1") (pintype "input"))
      (node (ref "R6") (pin "1") (pinfunction "1_1") (pintype "input"))
      (node (ref "R8") (pin "1") (pinfunction "1_1") (pintype "input"))
      (node (ref "R9") (pin "1") (pinfunction "1_1") (pintype "input"))
      (node (ref "U1") (pin "4") (pinfunction "VOUT_4") (pintype "input"))
      (node (ref "U1") (pin "5") (pinfunction "VOUT_5") (pintype "input"))
      (node (ref "U2") (pin "4") (pinfunction "VDD_4") (pintype "input"))
    )
    (net (code "2") (name "/BAT_+") (class "Default")
      (node (ref "C1") (pin "2") (pinfunction "2_2") (pintype "input"))
      (node (ref "U1") (pin "1") (pinfunction "EN_1") (pintype "input"))
      (node (ref "U1") (pin "2") (pinfunction "VIN_2") (pintype "input"))
    )
    (net (code "3") (name "/MOSFET") (class "Default")
      (node (ref "Q1") (pin "2") (pinfunction "G_2") (pintype "input"))
      (node (ref "R7") (pin "2") (pinfunction "2_2") (pintype "input"))
      (node (ref "U2") (pin "9") (pinfunction "PB5_9") (pintype "input"))
    )
    (net (code "4") (name "/SWITCH") (class "Default")
      (node (ref "LED10") (pin "1") (pinfunction "C_1") (pintype "input"))
      (node (ref "LED11") (pin "1") (pinfunction "C_1") (pintype "input"))
      (node (ref "LED12") (pin "1") (pinfunction "C_1") (pintype "input"))
      (node (ref "LED13") (pin "1") (pinfunction "C_1") (pintype "input"))
      (node (ref "LED14") (pin "1") (pinfunction "C_1") (pintype "input"))
      (node (ref "LED15") (pin "1") (pinfunction "C_1") (pintype "input"))
      (node (ref "LED16") (pin "1") (pinfunction "C_1") (pintype "input"))
      (node (ref "LED17") (pin "1") (pinfunction "C_1") (pintype "input"))
      (node (ref "LED18") (pin "1") (pinfunction "C_1") (pintype "input"))
      (node (ref "LED19") (pin "1") (pinfunction "C_1") (pintype "input"))
      (node (ref "LED2") (pin "1") (pinfunction "C_1") (pintype "input"))
      (node (ref "LED20") (pin "1") (pinfunction "C_1") (pintype "input"))
      (node (ref "LED21") (pin "1") (pinfunction "C_1") (pintype "input"))
      (node (ref "LED22") (pin "1") (pinfunction "C_1") (pintype "input"))
      (node (ref "LED23") (pin "1") (pinfunction "C_1") (pintype "input"))
      (node (ref "LED24") (pin "1") (pinfunction "C_1") (pintype "input"))
      (node (ref "LED25") (pin "1") (pinfunction "C_1") (pintype "input"))
      (node (ref "LED26") (pin "1") (pinfunction "C_1") (pintype "input"))
      (node (ref "LED27") (pin "1") (pinfunction "C_1") (pintype "input"))
      (node (ref "LED28") (pin "1") (pinfunction "C_1") (pintype "input"))
      (node (ref "LED29") (pin "1") (pinfunction "C_1") (pintype "input"))
      (node (ref "LED3") (pin "1") (pinfunction "C_1") (pintype "input"))
      (node (ref "LED30") (pin "1") (pinfunction "C_1") (pintype "input"))
      (node (ref "LED31") (pin "1") (pinfunction "C_1") (pintype "input"))
      (node (ref "LED32") (pin "1") (pinfunction "C_1") (pintype "input"))
      (node (ref "LED33") (pin "1") (pinfunction "C_1") (pintype "input"))
      (node (ref "LED34") (pin "1") (pinfunction "C_1") (pintype "input"))
      (node (ref "LED35") (pin "1") (pinfunction "C_1") (pintype "input"))
      (node (ref "LED36") (pin "1") (pinfunction "C_1") (pintype "input"))
      (node (ref "LED37") (pin "1") (pinfunction "C_1") (pintype "input"))
      (node (ref "LED38") (pin "1") (pinfunction "C_1") (pintype "input"))
      (node (ref "LED39") (pin "1") (pinfunction "C_1") (pintype "input"))
      (node (ref "LED4") (pin "1") (pinfunction "C_1") (pintype "input"))
      (node (ref "LED40") (pin "1") (pinfunction "C_1") (pintype "input"))
      (node (ref "LED41") (pin "1") (pinfunction "C_1") (pintype "input"))
      (node (ref "LED42") (pin "1") (pinfunction "C_1") (pintype "input"))
      (node (ref "LED43") (pin "1") (pinfunction "C_1") (pintype "input"))
      (node (ref "LED5") (pin "1") (pinfunction "C_1") (pintype "input"))
      (node (ref "LED6") (pin "1") (pinfunction "C_1") (pintype "input"))
      (node (ref "LED7") (pin "1") (pinfunction "C_1") (pintype "input"))
      (node (ref "LED8") (pin "1") (pinfunction "C_1") (pintype "input"))
      (node (ref "LED9") (pin "1") (pinfunction "C_1") (pintype "input"))
      (node (ref "Q1") (pin "3") (pinfunction "D_3") (pintype "input"))
    )
    (net (code "5") (name "/UDPI") (class "Default")
      (node (ref "U2") (pin "19") (pinfunction "PA0/RESET#/UPDI_19") (pintype "input"))
    )
    (net (code "6") (name "/VIB") (class "Default")
      (node (ref "R48") (pin "1") (pinfunction "1_1") (pintype "input"))
      (node (ref "SW1") (pin "2") (pinfunction "2_2") (pintype "input"))
      (node (ref "U2") (pin "11") (pinfunction "PB3/TOSC1_11") (pintype "input"))
    )
    (net (code "7") (name "GND") (class "Default")
      (node (ref "C1") (pin "1") (pinfunction "1_1") (pintype "input"))
      (node (ref "C10") (pin "1") (pinfunction "1_1") (pintype "input"))
      (node (ref "C11") (pin "1") (pinfunction "1_1") (pintype "input"))
      (node (ref "C12") (pin "1") (pinfunction "1_1") (pintype "input"))
      (node (ref "C13") (pin "1") (pinfunction "1_1") (pintype "input"))
      (node (ref "C14") (pin "1") (pinfunction "1_1") (pintype "input"))
      (node (ref "C15") (pin "1") (pinfunction "1_1") (pintype "input"))
      (node (ref "C16") (pin "1") (pinfunction "1_1") (pintype "input"))
      (node (ref "C17") (pin "1") (pinfunction "1_1") (pintype "input"))
      (node (ref "C18") (pin "1") (pinfunction "1_1") (pintype "input"))
      (node (ref "C19") (pin "1") (pinfunction "1_1") (pintype "input"))
      (node (ref "C2") (pin "1") (pinfunction "1_1") (pintype "input"))
      (node (ref "C20") (pin "1") (pinfunction "1_1") (pintype "input"))
      (node (ref "C21") (pin "1") (pinfunction "1_1") (pintype "input"))
      (node (ref "C22") (pin "1") (pinfunction "1_1") (pintype "input"))
      (node (ref "C23") (pin "1") (pinfunction "1_1") (pintype "input"))
      (node (ref "C24") (pin "1") (pinfunction "1_1") (pintype "input"))
      (node (ref "C3") (pin "1") (pinfunction "1_1") (pintype "input"))
      (node (ref "C4") (pin "1") (pinfunction "1_1") (pintype "input"))
      (node (ref "C45") (pin "1") (pinfunction "1_1") (pintype "input"))
      (node (ref "C46") (pin "1") (pinfunction "1_1") (pintype "input"))
      (node (ref "C5") (pin "1") (pinfunction "1_1") (pintype "input"))
      (node (ref "C6") (pin "1") (pinfunction "1_1") (pintype "input"))
      (node (ref "C7") (pin "1") (pinfunction "1_1") (pintype "input"))
      (node (ref "C8") (pin "1") (pinfunction "1_1") (pintype "input"))
      (node (ref "C9") (pin "1") (pinfunction "1_1") (pintype "input"))
      (node (ref "LED1") (pin "1") (pinfunction "-_1") (pintype "input"))
      (node (ref "Q1") (pin "1") (pinfunction "S_1") (pintype "input"))
      (node (ref "R3") (pin "1") (pinfunction "1_1") (pintype "unspecified"))
      (node (ref "R7") (pin "1") (pinfunction "1_1") (pintype "input"))
      (node (ref "SW1") (pin "1") (pinfunction "1_1") (pintype "input"))
      (node (ref "U1") (pin "3") (pinfunction "GND_3") (pintype "input"))
      (node (ref "U1") (pin "9") (pinfunction "EP_9") (pintype "input"))
      (node (ref "U2") (pin "3") (pinfunction "GND_3") (pintype "input"))
    )
    (net (code "8") (name "Net-(LED1-+)") (class "Default")
      (node (ref "LED1") (pin "2") (pinfunction "+_2") (pintype "input"))
      (node (ref "R4") (pin "1") (pinfunction "1_1") (pintype "input"))
    )
    (net (code "9") (name "Net-(LED2-A)") (class "Default")
      (node (ref "LED2") (pin "2") (pinfunction "A_2") (pintype "input"))
      (node (ref "R5") (pin "2") (pinfunction "2_2") (pintype "input"))
    )
    (net (code "10") (name "Net-(LED3-A)") (class "Default")
      (node (ref "LED3") (pin "2") (pinfunction "A_2") (pintype "input"))
      (node (ref "R6") (pin "2") (pinfunction "2_2") (pintype "input"))
    )
    (net (code "11") (name "Net-(LED4-A)") (class "Default")
      (node (ref "LED4") (pin "2") (pinfunction "A_2") (pintype "input"))
      (node (ref "R8") (pin "2") (pinfunction "2_2") (pintype "input"))
    )
    (net (code "12") (name "Net-(LED5-A)") (class "Default")
      (node (ref "LED5") (pin "2") (pinfunction "A_2") (pintype "input"))
      (node (ref "R9") (pin "2") (pinfunction "2_2") (pintype "input"))
    )
    (net (code "13") (name "Net-(LED6-A)") (class "Default")
      (node (ref "LED6") (pin "2") (pinfunction "A_2") (pintype "input"))
      (node (ref "R10") (pin "2") (pinfunction "2_2") (pintype "input"))
    )
    (net (code "14") (name "Net-(LED7-A)") (class "Default")
      (node (ref "LED7") (pin "2") (pinfunction "A_2") (pintype "input"))
      (node (ref "R11") (pin "2") (pinfunction "2_2") (pintype "input"))
    )
    (net (code "15") (name "Net-(LED8-A)") (class "Default")
      (node (ref "LED8") (pin "2") (pinfunction "A_2") (pintype "input"))
      (node (ref "R12") (pin "2") (pinfunction "2_2") (pintype "input"))
    )
    (net (code "16") (name "Net-(LED9-A)") (class "Default")
      (node (ref "LED9") (pin "2") (pinfunction "A_2") (pintype "input"))
      (node (ref "R13") (pin "2") (pinfunction "2_2") (pintype "input"))
    )
    (net (code "17") (name "Net-(LED10-A)") (class "Default")
      (node (ref "LED10") (pin "2") (pinfunction "A_2") (pintype "input"))
      (node (ref "R14") (pin "2") (pinfunction "2_2") (pintype "input"))
    )
    (net (code "18") (name "Net-(LED11-A)") (class "Default")
      (node (ref "LED11") (pin "2") (pinfunction "A_2") (pintype "input"))
      (node (ref "R15") (pin "2") (pinfunction "2_2") (pintype "input"))
    )
    (net (code "19") (name "Net-(LED12-A)") (class "Default")
      (node (ref "LED12") (pin "2") (pinfunction "A_2") (pintype "input"))
      (node (ref "R16") (pin "2") (pinfunction "2_2") (pintype "input"))
    )
    (net (code "20") (name "Net-(LED13-A)") (class "Default")
      (node (ref "LED13") (pin "2") (pinfunction "A_2") (pintype "input"))
      (node (ref "R17") (pin "2") (pinfunction "2_2") (pintype "input"))
    )
    (net (code "21") (name "Net-(LED14-A)") (class "Default")
      (node (ref "LED14") (pin "2") (pinfunction "A_2") (pintype "input"))
      (node (ref "R18") (pin "2") (pinfunction "2_2") (pintype "input"))
    )
    (net (code "22") (name "Net-(LED15-A)") (class "Default")
      (node (ref "LED15") (pin "2") (pinfunction "A_2") (pintype "input"))
      (node (ref "R19") (pin "2") (pinfunction "2_2") (pintype "input"))
    )
    (net (code "23") (name "Net-(LED16-A)") (class "Default")
      (node (ref "LED16") (pin "2") (pinfunction "A_2") (pintype "input"))
      (node (ref "R20") (pin "2") (pinfunction "2_2") (pintype "input"))
    )
    (net (code "24") (name "Net-(LED17-A)") (class "Default")
      (node (ref "LED17") (pin "2") (pinfunction "A_2") (pintype "input"))
      (node (ref "R21") (pin "2") (pinfunction "2_2") (pintype "input"))
    )
    (net (code "25") (name "Net-(LED18-A)") (class "Default")
      (node (ref "LED18") (pin "2") (pinfunction "A_2") (pintype "input"))
      (node (ref "R22") (pin "2") (pinfunction "2_2") (pintype "input"))
    )
    (net (code "26") (name "Net-(LED19-A)") (class "Default")
      (node (ref "LED19") (pin "2") (pinfunction "A_2") (pintype "input"))
      (node (ref "R23") (pin "2") (pinfunction "2_2") (pintype "input"))
    )
    (net (code "27") (name "Net-(LED20-A)") (class "Default")
      (node (ref "LED20") (pin "2") (pinfunction "A_2") (pintype "input"))
      (node (ref "R24") (pin "2") (pinfunction "2_2") (pintype "input"))
    )
    (net (code "28") (name "Net-(LED21-A)") (class "Default")
      (node (ref "LED21") (pin "2") (pinfunction "A_2") (pintype "input"))
      (node (ref "R25") (pin "2") (pinfunction "2_2") (pintype "input"))
    )
    (net (code "29") (name "Net-(LED22-A)") (class "Default")
      (node (ref "LED22") (pin "2") (pinfunction "A_2") (pintype "input"))
      (node (ref "R26") (pin "2") (pinfunction "2_2") (pintype "input"))
    )
    (net (code "30") (name "Net-(LED23-A)") (class "Default")
      (node (ref "LED23") (pin "2") (pinfunction "A_2") (pintype "input"))
      (node (ref "R27") (pin "2") (pinfunction "2_2") (pintype "input"))
    )
    (net (code "31") (name "Net-(LED24-A)") (class "Default")
      (node (ref "LED24") (pin "2") (pinfunction "A_2") (pintype "input"))
      (node (ref "R28") (pin "2") (pinfunction "2_2") (pintype "input"))
    )
    (net (code "32") (name "Net-(LED25-A)") (class "Default")
      (node (ref "LED25") (pin "2") (pinfunction "A_2") (pintype "input"))
      (node (ref "R29") (pin "2") (pinfunction "2_2") (pintype "input"))
    )
    (net (code "33") (name "Net-(LED26-A)") (class "Default")
      (node (ref "LED26") (pin "2") (pinfunction "A_2") (pintype "input"))
      (node (ref "R30") (pin "2") (pinfunction "2_2") (pintype "input"))
    )
    (net (code "34") (name "Net-(LED27-A)") (class "Default")
      (node (ref "LED27") (pin "2") (pinfunction "A_2") (pintype "input"))
      (node (ref "R31") (pin "2") (pinfunction "2_2") (pintype "input"))
    )
    (net (code "35") (name "Net-(LED28-A)") (class "Default")
      (node (ref "LED28") (pin "2") (pinfunction "A_2") (pintype "input"))
      (node (ref "R32") (pin "2") (pinfunction "2_2") (pintype "input"))
    )
    (net (code "36") (name "Net-(LED29-A)") (class "Default")
      (node (ref "LED29") (pin "2") (pinfunction "A_2") (pintype "input"))
      (node (ref "R33") (pin "2") (pinfunction "2_2") (pintype "input"))
    )
    (net (code "37") (name "Net-(LED30-A)") (class "Default")
      (node (ref "LED30") (pin "2") (pinfunction "A_2") (pintype "input"))
      (node (ref "R34") (pin "2") (pinfunction "2_2") (pintype "input"))
    )
    (net (code "38") (name "Net-(LED31-A)") (class "Default")
      (node (ref "LED31") (pin "2") (pinfunction "A_2") (pintype "input"))
      (node (ref "R35") (pin "2") (pinfunction "2_2") (pintype "input"))
    )
    (net (code "39") (name "Net-(LED32-A)") (class "Default")
      (node (ref "LED32") (pin "2") (pinfunction "A_2") (pintype "input"))
      (node (ref "R36") (pin "2") (pinfunction "2_2") (pintype "input"))
    )
    (net (code "40") (name "Net-(LED33-A)") (class "Default")
      (node (ref "LED33") (pin "2") (pinfunction "A_2") (pintype "input"))
      (node (ref "R37") (pin "2") (pinfunction "2_2") (pintype "input"))
    )
    (net (code "41") (name "Net-(LED34-A)") (class "Default")
      (node (ref "LED34") (pin "2") (pinfunction "A_2") (pintype "input"))
      (node (ref "R38") (pin "2") (pinfunction "2_2") (pintype "input"))
    )
    (net (code "42") (name "Net-(LED35-A)") (class "Default")
      (node (ref "LED35") (pin "2") (pinfunction "A_2") (pintype "input"))
      (node (ref "R39") (pin "2") (pinfunction "2_2") (pintype "input"))
    )
    (net (code "43") (name "Net-(LED36-A)") (class "Default")
      (node (ref "LED36") (pin "2") (pinfunction "A_2") (pintype "input"))
      (node (ref "R40") (pin "2") (pinfunction "2_2") (pintype "input"))
    )
    (net (code "44") (name "Net-(LED37-A)") (class "Default")
      (node (ref "LED37") (pin "2") (pinfunction "A_2") (pintype "input"))
      (node (ref "R41") (pin "2") (pinfunction "2_2") (pintype "input"))
    )
    (net (code "45") (name "Net-(LED38-A)") (class "Default")
      (node (ref "LED38") (pin "2") (pinfunction "A_2") (pintype "input"))
      (node (ref "R42") (pin "2") (pinfunction "2_2") (pintype "input"))
    )
    (net (code "46") (name "Net-(LED39-A)") (class "Default")
      (node (ref "LED39") (pin "2") (pinfunction "A_2") (pintype "input"))
      (node (ref "R43") (pin "2") (pinfunction "2_2") (pintype "input"))
    )
    (net (code "47") (name "Net-(LED40-A)") (class "Default")
      (node (ref "LED40") (pin "2") (pinfunction "A_2") (pintype "input"))
      (node (ref "R44") (pin "2") (pinfunction "2_2") (pintype "input"))
    )
    (net (code "48") (name "Net-(LED41-A)") (class "Default")
      (node (ref "LED41") (pin "2") (pinfunction "A_2") (pintype "input"))
      (node (ref "R45") (pin "2") (pinfunction "2_2") (pintype "input"))
    )
    (net (code "49") (name "Net-(LED42-A)") (class "Default")
      (node (ref "LED42") (pin "2") (pinfunction "A_2") (pintype "input"))
      (node (ref "R46") (pin "2") (pinfunction "2_2") (pintype "input"))
    )
    (net (code "50") (name "Net-(LED43-A)") (class "Default")
      (node (ref "LED43") (pin "2") (pinfunction "A_2") (pintype "input"))
      (node (ref "R47") (pin "2") (pinfunction "2_2") (pintype "input"))
    )
    (net (code "51") (name "Net-(U1-FB)") (class "Default")
      (node (ref "R2") (pin "1") (pinfunction "1_1") (pintype "input"))
      (node (ref "R3") (pin "2") (pinfunction "2_2") (pintype "unspecified"))
      (node (ref "U1") (pin "6") (pinfunction "FB_6") (pintype "input"))
    )
    (net (code "52") (name "Net-(U1-PG)") (class "Default")
      (node (ref "R1") (pin "1") (pinfunction "1_1") (pintype "unspecified"))
      (node (ref "U1") (pin "7") (pinfunction "PG_7") (pintype "input"))
    )
    (net (code "53") (name "Net-(U1-SS{slash}TR)") (class "Default")
      (node (ref "C3") (pin "2") (pinfunction "2_2") (pintype "input"))
      (node (ref "U1") (pin "8") (pinfunction "SS/TR_8") (pintype "input"))
    )
    (net (code "54") (name "Net-(U2-PA4)") (class "Default")
      (node (ref "R4") (pin "2") (pinfunction "2_2") (pintype "input"))
      (node (ref "U2") (pin "5") (pinfunction "PA4_5") (pintype "input"))
    )
    (net (code "55") (name "unconnected-(U2-EP-Pad21)") (class "Default")
      (node (ref "U2") (pin "21") (pinfunction "EP_21") (pintype "input"))
    )
    (net (code "56") (name "unconnected-(U2-EXTCLK{slash}PA3-Pad2)") (class "Default")
      (node (ref "U2") (pin "2") (pinfunction "EXTCLK/PA3_2") (pintype "input"))
    )
    (net (code "57") (name "unconnected-(U2-PA1-Pad20)") (class "Default")
      (node (ref "U2") (pin "20") (pinfunction "PA1_20") (pintype "input"))
    )
    (net (code "58") (name "unconnected-(U2-PA2-Pad1)") (class "Default")
      (node (ref "U2") (pin "1") (pinfunction "PA2_1") (pintype "input"))
    )
    (net (code "59") (name "unconnected-(U2-PA5-Pad6)") (class "Default")
      (node (ref "U2") (pin "6") (pinfunction "PA5_6") (pintype "input"))
    )
    (net (code "60") (name "unconnected-(U2-PA6-Pad7)") (class "Default")
      (node (ref "U2") (pin "7") (pinfunction "PA6_7") (pintype "input"))
    )
    (net (code "61") (name "unconnected-(U2-PA7-Pad8)") (class "Default")
      (node (ref "U2") (pin "8") (pinfunction "PA7_8") (pintype "input"))
    )
    (net (code "62") (name "unconnected-(U2-PB0-Pad14)") (class "Default")
      (node (ref "U2") (pin "14") (pinfunction "PB0_14") (pintype "input"))
    )
    (net (code "63") (name "unconnected-(U2-PB1-Pad13)") (class "Default")
      (node (ref "U2") (pin "13") (pinfunction "PB1_13") (pintype "input"))
    )
    (net (code "64") (name "unconnected-(U2-PB2{slash}TOSC2-Pad12)") (class "Default")
      (node (ref "U2") (pin "12") (pinfunction "PB2/TOSC2_12") (pintype "input"))
    )
    (net (code "65") (name "unconnected-(U2-PB4-Pad10)") (class "Default")
      (node (ref "U2") (pin "10") (pinfunction "PB4_10") (pintype "input"))
    )
    (net (code "66") (name "unconnected-(U2-PC0-Pad15)") (class "Default")
      (node (ref "U2") (pin "15") (pinfunction "PC0_15") (pintype "input"))
    )
    (net (code "67") (name "unconnected-(U2-PC1-Pad16)") (class "Default")
      (node (ref "U2") (pin "16") (pinfunction "PC1_16") (pintype "input"))
    )
    (net (code "68") (name "unconnected-(U2-PC2-Pad17)") (class "Default")
      (node (ref "U2") (pin "17") (pinfunction "PC2_17") (pintype "input"))
    )
    (net (code "69") (name "unconnected-(U2-PC3-Pad18)") (class "Default")
      (node (ref "U2") (pin "18") (pinfunction "PC3_18") (pintype "input"))
    )
  )
)
